# pcb_3170100699.net
KiCad netlist of a schematic drawn in Altium Designer
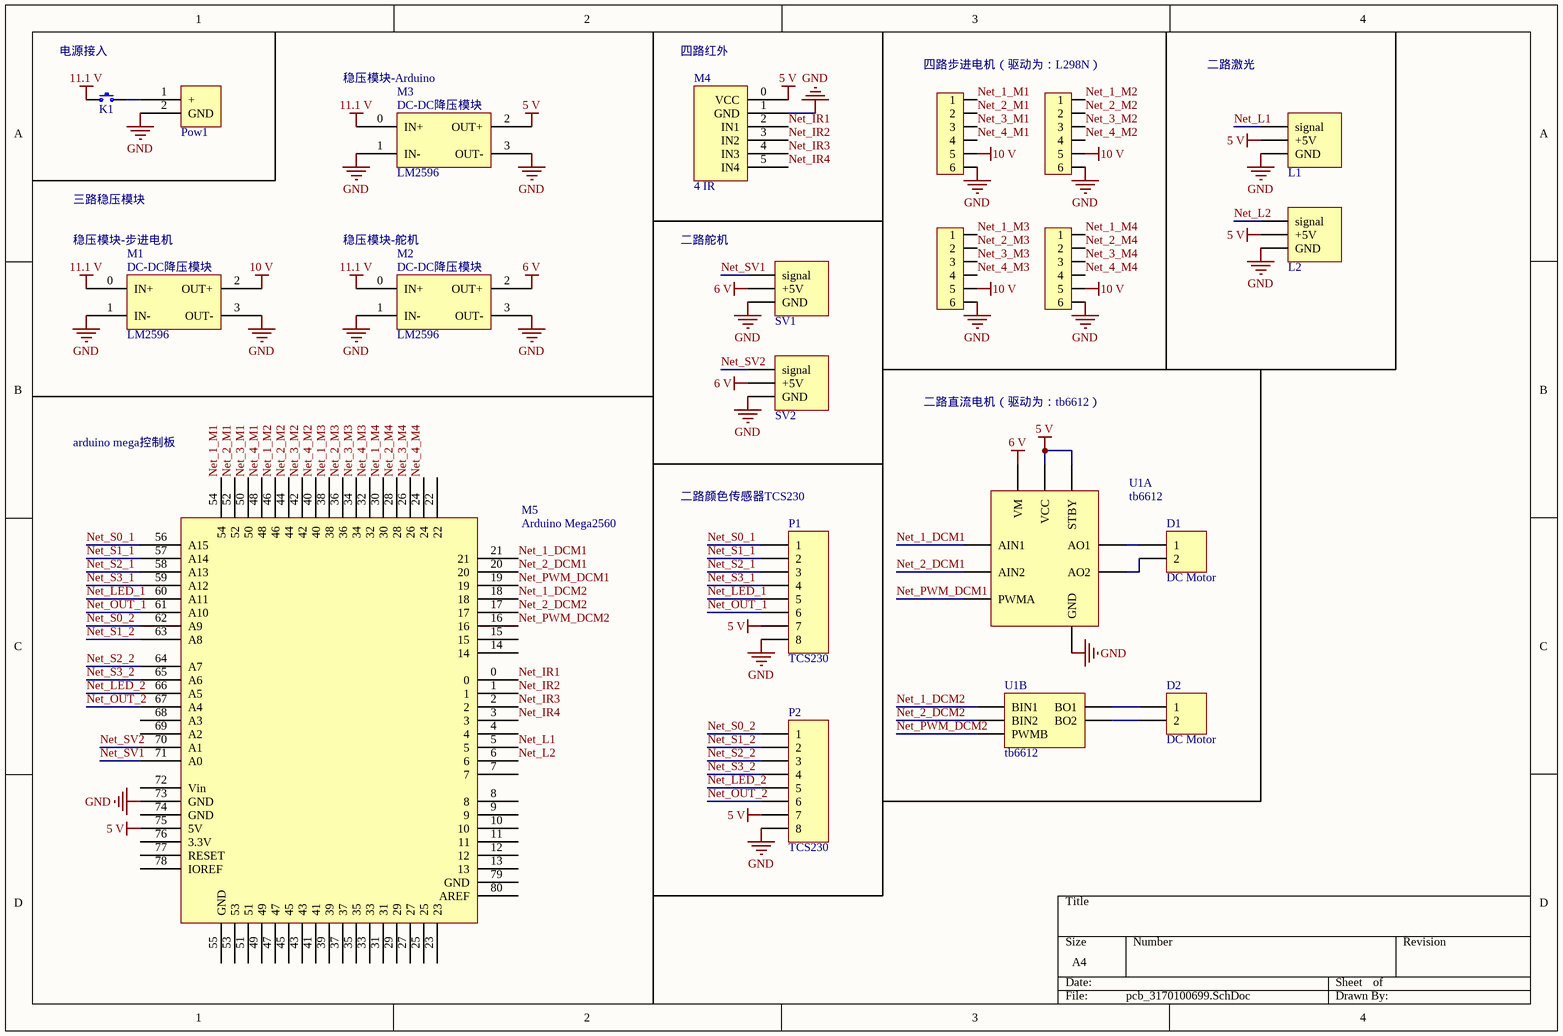
[diagram p0: pcb_3170100699.SchDoc]

(export (version "E")
  (design (tool "Eeschema 10.0.6"))
  (components
    (comp (ref "D1")
      (value "DC Motor")
      (footprint "HDR1X2")
      (description "Header, 2-Pin")
      (fields (field (name "PUBLISHER") "Altium Limited"))
      (libsource (lib "Miscellaneous Connectors") (part "Header 2"))
    )
    (comp (ref "D2")
      (value "DC Motor")
      (footprint "HDR1X2")
      (description "Header, 2-Pin")
      (fields (field (name "PUBLISHER") "Altium Limited"))
      (libsource (lib "Miscellaneous Connectors") (part "Header 2"))
    )
    (comp (ref "K1") (value "key") (footprint "Header2") (libsource (lib "edition1") (part "key")))
    (comp (ref "L1") (value "SERVO") (footprint "SIP3-1") (libsource (lib "edition1") (part "SERVO")))
    (comp (ref "L2") (value "SERVO") (footprint "SIP3-1") (libsource (lib "edition1") (part "SERVO")))
    (comp (ref "M1") (value "LM2596") (footprint "DC-DC降压") (libsource (lib "edition1") (part "LM2596")))
    (comp (ref "M2") (value "LM2596") (footprint "DC-DC降压") (libsource (lib "edition1") (part "LM2596")))
    (comp (ref "M3") (value "LM2596") (footprint "DC-DC降压") (libsource (lib "edition1") (part "LM2596")))
    (comp (ref "M4")
      (value "4 IR")
      (footprint "4 infrared avoidance - duplicate")
      (libsource (lib "edition1") (part "4 IR"))
    )
    (comp (ref "M5")
      (value "Arduino Mega2560")
      (footprint "Arduino Mega2560")
      (libsource (lib "edition1") (part "Arduino Mega2560"))
    )
    (comp (ref "P1")
      (value "TCS230")
      (footprint "HDR1X8")
      (description "Header, 8-Pin")
      (fields (field (name "PUBLISHER") "Altium Limited"))
      (libsource (lib "Miscellaneous Connectors") (part "Header 8"))
    )
    (comp (ref "P2")
      (value "TCS230")
      (footprint "HDR1X8")
      (description "Header, 8-Pin")
      (fields (field (name "PUBLISHER") "Altium Limited"))
      (libsource (lib "Miscellaneous Connectors") (part "Header 8"))
    )
    (comp (ref "Pow1") (value "POWER") (footprint "Power") (libsource (lib "edition1") (part "POWER")))
    (comp (ref "SMotor1") (value "SMotor") (footprint "SIP6-1") (libsource (lib "edition1") (part "SIP6")))
    (comp (ref "SMotor2") (value "SMotor") (footprint "SIP6-1") (libsource (lib "edition1") (part "SIP6")))
    (comp (ref "SMotor3") (value "SMotor") (footprint "SIP6-1") (libsource (lib "edition1") (part "SIP6")))
    (comp (ref "SMotor4") (value "SMotor") (footprint "SIP6-1") (libsource (lib "edition1") (part "SIP6")))
    (comp (ref "SV1") (value "SERVO") (footprint "SIP3-1") (libsource (lib "edition1") (part "SERVO")))
    (comp (ref "SV2") (value "SERVO") (footprint "SIP3-1") (libsource (lib "edition1") (part "SERVO")))
    (comp (ref "U1") (value "tb6612") (footprint "tb6612") (libsource (lib "edition1") (part "tb6612")))
  )
  (nets
    (net (code "1") (name "/Net_1_DCM1") (class "Default")
      (node (ref "M5") (pin "21") (pinfunction "21_21") (pintype "passive"))
      (node (ref "U1") (pin "14") (pinfunction "AIN1_14") (pintype "passive"))
    )
    (net (code "2") (name "/Net_1_DCM2") (class "Default")
      (node (ref "M5") (pin "18") (pinfunction "18_18") (pintype "passive"))
      (node (ref "U1") (pin "12") (pinfunction "BIN1_12") (pintype "passive"))
    )
    (net (code "3") (name "/Net_1_M1") (class "Default")
      (node (ref "M5") (pin "54") (pinfunction "54_54") (pintype "passive"))
      (node (ref "SMotor1") (pin "1") (pinfunction "1_1") (pintype "passive"))
    )
    (net (code "4") (name "/Net_1_M2") (class "Default")
      (node (ref "M5") (pin "46") (pinfunction "46_46") (pintype "passive"))
      (node (ref "SMotor2") (pin "1") (pinfunction "1_1") (pintype "passive"))
    )
    (net (code "5") (name "/Net_1_M3") (class "Default")
      (node (ref "M5") (pin "38") (pinfunction "38_38") (pintype "passive"))
      (node (ref "SMotor3") (pin "1") (pinfunction "1_1") (pintype "passive"))
    )
    (net (code "6") (name "/Net_1_M4") (class "Default")
      (node (ref "M5") (pin "30") (pinfunction "30_30") (pintype "passive"))
      (node (ref "SMotor4") (pin "1") (pinfunction "1_1") (pintype "passive"))
    )
    (net (code "7") (name "/Net_2_DCM1") (class "Default")
      (node (ref "M5") (pin "20") (pinfunction "20_20") (pintype "passive"))
      (node (ref "U1") (pin "15") (pinfunction "AIN2_15") (pintype "passive"))
    )
    (net (code "8") (name "/Net_2_DCM2") (class "Default")
      (node (ref "M5") (pin "17") (pinfunction "17_17") (pintype "passive"))
      (node (ref "U1") (pin "11") (pinfunction "BIN2_11") (pintype "passive"))
    )
    (net (code "9") (name "/Net_2_M1") (class "Default")
      (node (ref "M5") (pin "52") (pinfunction "52_52") (pintype "passive"))
      (node (ref "SMotor1") (pin "2") (pinfunction "2_2") (pintype "passive"))
    )
    (net (code "10") (name "/Net_2_M2") (class "Default")
      (node (ref "M5") (pin "44") (pinfunction "44_44") (pintype "passive"))
      (node (ref "SMotor2") (pin "2") (pinfunction "2_2") (pintype "passive"))
    )
    (net (code "11") (name "/Net_2_M3") (class "Default")
      (node (ref "M5") (pin "36") (pinfunction "36_36") (pintype "passive"))
      (node (ref "SMotor3") (pin "2") (pinfunction "2_2") (pintype "passive"))
    )
    (net (code "12") (name "/Net_2_M4") (class "Default")
      (node (ref "M5") (pin "28") (pinfunction "28_28") (pintype "passive"))
      (node (ref "SMotor4") (pin "2") (pinfunction "2_2") (pintype "passive"))
    )
    (net (code "13") (name "/Net_3_M1") (class "Default")
      (node (ref "M5") (pin "50") (pinfunction "50_50") (pintype "passive"))
      (node (ref "SMotor1") (pin "3") (pinfunction "3_3") (pintype "passive"))
    )
    (net (code "14") (name "/Net_3_M2") (class "Default")
      (node (ref "M5") (pin "42") (pinfunction "42_42") (pintype "passive"))
      (node (ref "SMotor2") (pin "3") (pinfunction "3_3") (pintype "passive"))
    )
    (net (code "15") (name "/Net_3_M3") (class "Default")
      (node (ref "M5") (pin "34") (pinfunction "34_34") (pintype "passive"))
      (node (ref "SMotor3") (pin "3") (pinfunction "3_3") (pintype "passive"))
    )
    (net (code "16") (name "/Net_3_M4") (class "Default")
      (node (ref "M5") (pin "26") (pinfunction "26_26") (pintype "passive"))
      (node (ref "SMotor4") (pin "3") (pinfunction "3_3") (pintype "passive"))
    )
    (net (code "17") (name "/Net_4_M1") (class "Default")
      (node (ref "M5") (pin "48") (pinfunction "48_48") (pintype "passive"))
      (node (ref "SMotor1") (pin "4") (pinfunction "4_4") (pintype "passive"))
    )
    (net (code "18") (name "/Net_4_M2") (class "Default")
      (node (ref "M5") (pin "40") (pinfunction "40_40") (pintype "passive"))
      (node (ref "SMotor2") (pin "4") (pinfunction "4_4") (pintype "passive"))
    )
    (net (code "19") (name "/Net_4_M3") (class "Default")
      (node (ref "M5") (pin "32") (pinfunction "32_32") (pintype "passive"))
      (node (ref "SMotor3") (pin "4") (pinfunction "4_4") (pintype "passive"))
    )
    (net (code "20") (name "/Net_4_M4") (class "Default")
      (node (ref "M5") (pin "24") (pinfunction "24_24") (pintype "passive"))
      (node (ref "SMotor4") (pin "4") (pinfunction "4_4") (pintype "passive"))
    )
    (net (code "21") (name "/Net_IR1") (class "Default")
      (node (ref "M4") (pin "2") (pinfunction "IN1_2") (pintype "passive"))
      (node (ref "M5") (pin "0") (pinfunction "0_0") (pintype "passive"))
    )
    (net (code "22") (name "/Net_IR2") (class "Default")
      (node (ref "M4") (pin "3") (pinfunction "IN2_3") (pintype "passive"))
      (node (ref "M5") (pin "1") (pinfunction "1_1") (pintype "passive"))
    )
    (net (code "23") (name "/Net_IR3") (class "Default")
      (node (ref "M4") (pin "4") (pinfunction "IN3_4") (pintype "passive"))
      (node (ref "M5") (pin "2") (pinfunction "2_2") (pintype "passive"))
    )
    (net (code "24") (name "/Net_IR4") (class "Default")
      (node (ref "M4") (pin "5") (pinfunction "IN4_5") (pintype "passive"))
      (node (ref "M5") (pin "3") (pinfunction "3_3") (pintype "passive"))
    )
    (net (code "25") (name "/Net_L1") (class "Default")
      (node (ref "L1") (pin "1") (pinfunction "signal_1") (pintype "passive"))
      (node (ref "M5") (pin "5") (pinfunction "5_5") (pintype "passive"))
    )
    (net (code "26") (name "/Net_L2") (class "Default")
      (node (ref "L2") (pin "1") (pinfunction "signal_1") (pintype "passive"))
      (node (ref "M5") (pin "6") (pinfunction "6_6") (pintype "passive"))
    )
    (net (code "27") (name "/Net_LED_1") (class "Default")
      (node (ref "M5") (pin "60") (pinfunction "A11_60") (pintype "passive"))
      (node (ref "P1") (pin "5") (pinfunction "5_5") (pintype "passive"))
    )
    (net (code "28") (name "/Net_LED_2") (class "Default")
      (node (ref "M5") (pin "66") (pinfunction "A5_66") (pintype "passive"))
      (node (ref "P2") (pin "5") (pinfunction "5_5") (pintype "passive"))
    )
    (net (code "29") (name "/Net_OUT_1") (class "Default")
      (node (ref "M5") (pin "61") (pinfunction "A10_61") (pintype "passive"))
      (node (ref "P1") (pin "6") (pinfunction "6_6") (pintype "passive"))
    )
    (net (code "30") (name "/Net_OUT_2") (class "Default")
      (node (ref "M5") (pin "67") (pinfunction "A4_67") (pintype "passive"))
      (node (ref "P2") (pin "6") (pinfunction "6_6") (pintype "passive"))
    )
    (net (code "31") (name "/Net_PWM_DCM1") (class "Default")
      (node (ref "M5") (pin "19") (pinfunction "19_19") (pintype "passive"))
      (node (ref "U1") (pin "16") (pinfunction "PWMA_16") (pintype "passive"))
    )
    (net (code "32") (name "/Net_PWM_DCM2") (class "Default")
      (node (ref "M5") (pin "16") (pinfunction "16_16") (pintype "passive"))
      (node (ref "U1") (pin "10") (pinfunction "PWMB_10") (pintype "passive"))
    )
    (net (code "33") (name "/Net_S0_1") (class "Default")
      (node (ref "M5") (pin "56") (pinfunction "A15_56") (pintype "passive"))
      (node (ref "P1") (pin "1") (pinfunction "1_1") (pintype "passive"))
    )
    (net (code "34") (name "/Net_S0_2") (class "Default")
      (node (ref "M5") (pin "62") (pinfunction "A9_62") (pintype "passive"))
      (node (ref "P2") (pin "1") (pinfunction "1_1") (pintype "passive"))
    )
    (net (code "35") (name "/Net_S1_1") (class "Default")
      (node (ref "M5") (pin "57") (pinfunction "A14_57") (pintype "passive"))
      (node (ref "P1") (pin "2") (pinfunction "2_2") (pintype "passive"))
    )
    (net (code "36") (name "/Net_S1_2") (class "Default")
      (node (ref "M5") (pin "63") (pinfunction "A8_63") (pintype "passive"))
      (node (ref "P2") (pin "2") (pinfunction "2_2") (pintype "passive"))
    )
    (net (code "37") (name "/Net_S2_1") (class "Default")
      (node (ref "M5") (pin "58") (pinfunction "A13_58") (pintype "passive"))
      (node (ref "P1") (pin "3") (pinfunction "3_3") (pintype "passive"))
    )
    (net (code "38") (name "/Net_S2_2") (class "Default")
      (node (ref "M5") (pin "64") (pinfunction "A7_64") (pintype "passive"))
      (node (ref "P2") (pin "3") (pinfunction "3_3") (pintype "passive"))
    )
    (net (code "39") (name "/Net_S3_1") (class "Default")
      (node (ref "M5") (pin "59") (pinfunction "A12_59") (pintype "passive"))
      (node (ref "P1") (pin "4") (pinfunction "4_4") (pintype "passive"))
    )
    (net (code "40") (name "/Net_S3_2") (class "Default")
      (node (ref "M5") (pin "65") (pinfunction "A6_65") (pintype "passive"))
      (node (ref "P2") (pin "4") (pinfunction "4_4") (pintype "passive"))
    )
    (net (code "41") (name "/Net_SV1") (class "Default")
      (node (ref "M5") (pin "71") (pinfunction "A0_71") (pintype "passive"))
      (node (ref "SV1") (pin "1") (pinfunction "signal_1") (pintype "passive"))
    )
    (net (code "42") (name "/Net_SV2") (class "Default")
      (node (ref "M5") (pin "70") (pinfunction "A1_70") (pintype "passive"))
      (node (ref "SV2") (pin "1") (pinfunction "signal_1") (pintype "passive"))
    )
    (net (code "43") (name "5 V") (class "Default")
      (node (ref "L1") (pin "2") (pinfunction "+5V_2") (pintype "passive"))
      (node (ref "L2") (pin "2") (pinfunction "+5V_2") (pintype "passive"))
      (node (ref "M3") (pin "2") (pinfunction "OUT+_2") (pintype "passive"))
      (node (ref "M4") (pin "0") (pinfunction "VCC_0") (pintype "passive"))
      (node (ref "M5") (pin "75") (pinfunction "5V_75") (pintype "passive"))
      (node (ref "P1") (pin "7") (pinfunction "7_7") (pintype "passive"))
      (node (ref "P2") (pin "7") (pinfunction "7_7") (pintype "passive"))
      (node (ref "U1") (pin "13") (pinfunction "STBY_13") (pintype "passive"))
      (node (ref "U1") (pin "2") (pinfunction "VCC_2") (pintype "passive"))
    )
    (net (code "44") (name "6 V") (class "Default")
      (node (ref "M2") (pin "2") (pinfunction "OUT+_2") (pintype "passive"))
      (node (ref "SV1") (pin "2") (pinfunction "+5V_2") (pintype "passive"))
      (node (ref "SV2") (pin "2") (pinfunction "+5V_2") (pintype "passive"))
      (node (ref "U1") (pin "1") (pinfunction "VM_1") (pintype "passive"))
    )
    (net (code "45") (name "10 V") (class "Default")
      (node (ref "M1") (pin "2") (pinfunction "OUT+_2") (pintype "passive"))
      (node (ref "SMotor1") (pin "5") (pinfunction "5_5") (pintype "passive"))
      (node (ref "SMotor2") (pin "5") (pinfunction "5_5") (pintype "passive"))
      (node (ref "SMotor3") (pin "5") (pinfunction "5_5") (pintype "passive"))
      (node (ref "SMotor4") (pin "5") (pinfunction "5_5") (pintype "passive"))
    )
    (net (code "46") (name "11.1 V") (class "Default")
      (node (ref "K1") (pin "1") (pinfunction "1_1") (pintype "passive"))
      (node (ref "M1") (pin "0") (pinfunction "IN+_0") (pintype "passive"))
      (node (ref "M2") (pin "0") (pinfunction "IN+_0") (pintype "passive"))
      (node (ref "M3") (pin "0") (pinfunction "IN+_0") (pintype "passive"))
    )
    (net (code "47") (name "GND") (class "Default")
      (node (ref "L1") (pin "3") (pinfunction "GND_3") (pintype "passive"))
      (node (ref "L2") (pin "3") (pinfunction "GND_3") (pintype "passive"))
      (node (ref "M1") (pin "1") (pinfunction "IN-_1") (pintype "passive"))
      (node (ref "M1") (pin "3") (pinfunction "OUT-_3") (pintype "passive"))
      (node (ref "M2") (pin "1") (pinfunction "IN-_1") (pintype "passive"))
      (node (ref "M2") (pin "3") (pinfunction "OUT-_3") (pintype "passive"))
      (node (ref "M3") (pin "1") (pinfunction "IN-_1") (pintype "passive"))
      (node (ref "M3") (pin "3") (pinfunction "OUT-_3") (pintype "passive"))
      (node (ref "M4") (pin "1") (pinfunction "GND_1") (pintype "passive"))
      (node (ref "M5") (pin "73") (pinfunction "GND_73") (pintype "passive"))
      (node (ref "P1") (pin "8") (pinfunction "8_8") (pintype "passive"))
      (node (ref "P2") (pin "8") (pinfunction "8_8") (pintype "passive"))
      (node (ref "Pow1") (pin "2") (pinfunction "GND_2") (pintype "passive"))
      (node (ref "SMotor1") (pin "6") (pinfunction "6_6") (pintype "passive"))
      (node (ref "SMotor2") (pin "6") (pinfunction "6_6") (pintype "passive"))
      (node (ref "SMotor3") (pin "6") (pinfunction "6_6") (pintype "passive"))
      (node (ref "SMotor4") (pin "6") (pinfunction "6_6") (pintype "passive"))
      (node (ref "SV1") (pin "3") (pinfunction "GND_3") (pintype "passive"))
      (node (ref "SV2") (pin "3") (pinfunction "GND_3") (pintype "passive"))
      (node (ref "U1") (pin "8") (pinfunction "GND_8") (pintype "passive"))
    )
    (net (code "48") (name "Net-(Pow1-+)") (class "Default")
      (node (ref "K1") (pin "2") (pinfunction "2_2") (pintype "passive"))
      (node (ref "Pow1") (pin "1") (pinfunction "+_1") (pintype "passive"))
    )
    (net (code "49") (name "Net-(U1A-AO1)") (class "Default")
      (node (ref "D1") (pin "1") (pinfunction "1_1") (pintype "passive"))
      (node (ref "U1") (pin "4") (pinfunction "AO1_4") (pintype "passive"))
    )
    (net (code "50") (name "Net-(U1A-AO2)") (class "Default")
      (node (ref "D1") (pin "2") (pinfunction "2_2") (pintype "passive"))
      (node (ref "U1") (pin "5") (pinfunction "AO2_5") (pintype "passive"))
    )
    (net (code "51") (name "Net-(U1B-BO1)") (class "Default")
      (node (ref "D2") (pin "1") (pinfunction "1_1") (pintype "passive"))
      (node (ref "U1") (pin "7") (pinfunction "BO1_7") (pintype "passive"))
    )
    (net (code "52") (name "Net-(U1B-BO2)") (class "Default")
      (node (ref "D2") (pin "2") (pinfunction "2_2") (pintype "passive"))
      (node (ref "U1") (pin "6") (pinfunction "BO2_6") (pintype "passive"))
    )
    (net (code "53") (name "unconnected-(M5-3.3V-Pad76)") (class "Default")
      (node (ref "M5") (pin "76") (pinfunction "3.3V_76") (pintype "passive"))
    )
    (net (code "54") (name "unconnected-(M5-A2-Pad69)") (class "Default")
      (node (ref "M5") (pin "69") (pinfunction "A2_69") (pintype "passive"))
    )
    (net (code "55") (name "unconnected-(M5-A3-Pad68)") (class "Default")
      (node (ref "M5") (pin "68") (pinfunction "A3_68") (pintype "passive"))
    )
    (net (code "56") (name "unconnected-(M5-AREF-Pad80)") (class "Default")
      (node (ref "M5") (pin "80") (pinfunction "AREF_80") (pintype "passive"))
    )
    (net (code "57") (name "unconnected-(M5-GND-Pad55)") (class "Default")
      (node (ref "M5") (pin "55") (pinfunction "GND_55") (pintype "passive"))
    )
    (net (code "58") (name "unconnected-(M5-GND-Pad74)") (class "Default")
      (node (ref "M5") (pin "74") (pinfunction "GND_74") (pintype "passive"))
    )
    (net (code "59") (name "unconnected-(M5-GND-Pad79)") (class "Default")
      (node (ref "M5") (pin "79") (pinfunction "GND_79") (pintype "passive"))
    )
    (net (code "60") (name "unconnected-(M5-IOREF-Pad78)") (class "Default")
      (node (ref "M5") (pin "78") (pinfunction "IOREF_78") (pintype "passive"))
    )
    (net (code "61") (name "unconnected-(M5-Pad4)") (class "Default")
      (node (ref "M5") (pin "4") (pinfunction "4_4") (pintype "passive"))
    )
    (net (code "62") (name "unconnected-(M5-Pad7)") (class "Default")
      (node (ref "M5") (pin "7") (pinfunction "7_7") (pintype "passive"))
    )
    (net (code "63") (name "unconnected-(M5-Pad8)") (class "Default")
      (node (ref "M5") (pin "8") (pinfunction "8_8") (pintype "passive"))
    )
    (net (code "64") (name "unconnected-(M5-Pad9)") (class "Default")
      (node (ref "M5") (pin "9") (pinfunction "9_9") (pintype "passive"))
    )
    (net (code "65") (name "unconnected-(M5-Pad10)") (class "Default")
      (node (ref "M5") (pin "10") (pinfunction "10_10") (pintype "passive"))
    )
    (net (code "66") (name "unconnected-(M5-Pad11)") (class "Default")
      (node (ref "M5") (pin "11") (pinfunction "11_11") (pintype "passive"))
    )
    (net (code "67") (name "unconnected-(M5-Pad12)") (class "Default")
      (node (ref "M5") (pin "12") (pinfunction "12_12") (pintype "passive"))
    )
    (net (code "68") (name "unconnected-(M5-Pad13)") (class "Default")
      (node (ref "M5") (pin "13") (pinfunction "13_13") (pintype "passive"))
    )
    (net (code "69") (name "unconnected-(M5-Pad14)") (class "Default")
      (node (ref "M5") (pin "14") (pinfunction "14_14") (pintype "passive"))
    )
    (net (code "70") (name "unconnected-(M5-Pad15)") (class "Default")
      (node (ref "M5") (pin "15") (pinfunction "15_15") (pintype "passive"))
    )
    (net (code "71") (name "unconnected-(M5-Pad22)") (class "Default")
      (node (ref "M5") (pin "22") (pinfunction "22_22") (pintype "passive"))
    )
    (net (code "72") (name "unconnected-(M5-Pad23)") (class "Default")
      (node (ref "M5") (pin "23") (pinfunction "23_23") (pintype "passive"))
    )
    (net (code "73") (name "unconnected-(M5-Pad25)") (class "Default")
      (node (ref "M5") (pin "25") (pinfunction "25_25") (pintype "passive"))
    )
    (net (code "74") (name "unconnected-(M5-Pad27)") (class "Default")
      (node (ref "M5") (pin "27") (pinfunction "27_27") (pintype "passive"))
    )
    (net (code "75") (name "unconnected-(M5-Pad29)") (class "Default")
      (node (ref "M5") (pin "29") (pinfunction "29_29") (pintype "passive"))
    )
    (net (code "76") (name "unconnected-(M5-Pad31)") (class "Default")
      (node (ref "M5") (pin "31") (pinfunction "31_31") (pintype "passive"))
    )
    (net (code "77") (name "unconnected-(M5-Pad33)") (class "Default")
      (node (ref "M5") (pin "33") (pinfunction "33_33") (pintype "passive"))
    )
    (net (code "78") (name "unconnected-(M5-Pad35)") (class "Default")
      (node (ref "M5") (pin "35") (pinfunction "35_35") (pintype "passive"))
    )
    (net (code "79") (name "unconnected-(M5-Pad37)") (class "Default")
      (node (ref "M5") (pin "37") (pinfunction "37_37") (pintype "passive"))
    )
    (net (code "80") (name "unconnected-(M5-Pad39)") (class "Default")
      (node (ref "M5") (pin "39") (pinfunction "39_39") (pintype "passive"))
    )
    (net (code "81") (name "unconnected-(M5-Pad41)") (class "Default")
      (node (ref "M5") (pin "41") (pinfunction "41_41") (pintype "passive"))
    )
    (net (code "82") (name "unconnected-(M5-Pad43)") (class "Default")
      (node (ref "M5") (pin "43") (pinfunction "43_43") (pintype "passive"))
    )
    (net (code "83") (name "unconnected-(M5-Pad45)") (class "Default")
      (node (ref "M5") (pin "45") (pinfunction "45_45") (pintype "passive"))
    )
    (net (code "84") (name "unconnected-(M5-Pad47)") (class "Default")
      (node (ref "M5") (pin "47") (pinfunction "47_47") (pintype "passive"))
    )
    (net (code "85") (name "unconnected-(M5-Pad49)") (class "Default")
      (node (ref "M5") (pin "49") (pinfunction "49_49") (pintype "passive"))
    )
    (net (code "86") (name "unconnected-(M5-Pad51)") (class "Default")
      (node (ref "M5") (pin "51") (pinfunction "51_51") (pintype "passive"))
    )
    (net (code "87") (name "unconnected-(M5-Pad53)") (class "Default")
      (node (ref "M5") (pin "53") (pinfunction "53_53") (pintype "passive"))
    )
    (net (code "88") (name "unconnected-(M5-RESET-Pad77)") (class "Default")
      (node (ref "M5") (pin "77") (pinfunction "RESET_77") (pintype "passive"))
    )
    (net (code "89") (name "unconnected-(M5-Vin-Pad72)") (class "Default")
      (node (ref "M5") (pin "72") (pinfunction "Vin_72") (pintype "passive"))
    )
  )
)
